# automatic_Slider_door_2.net
KiCad netlist of a schematic drawn in EAGLE
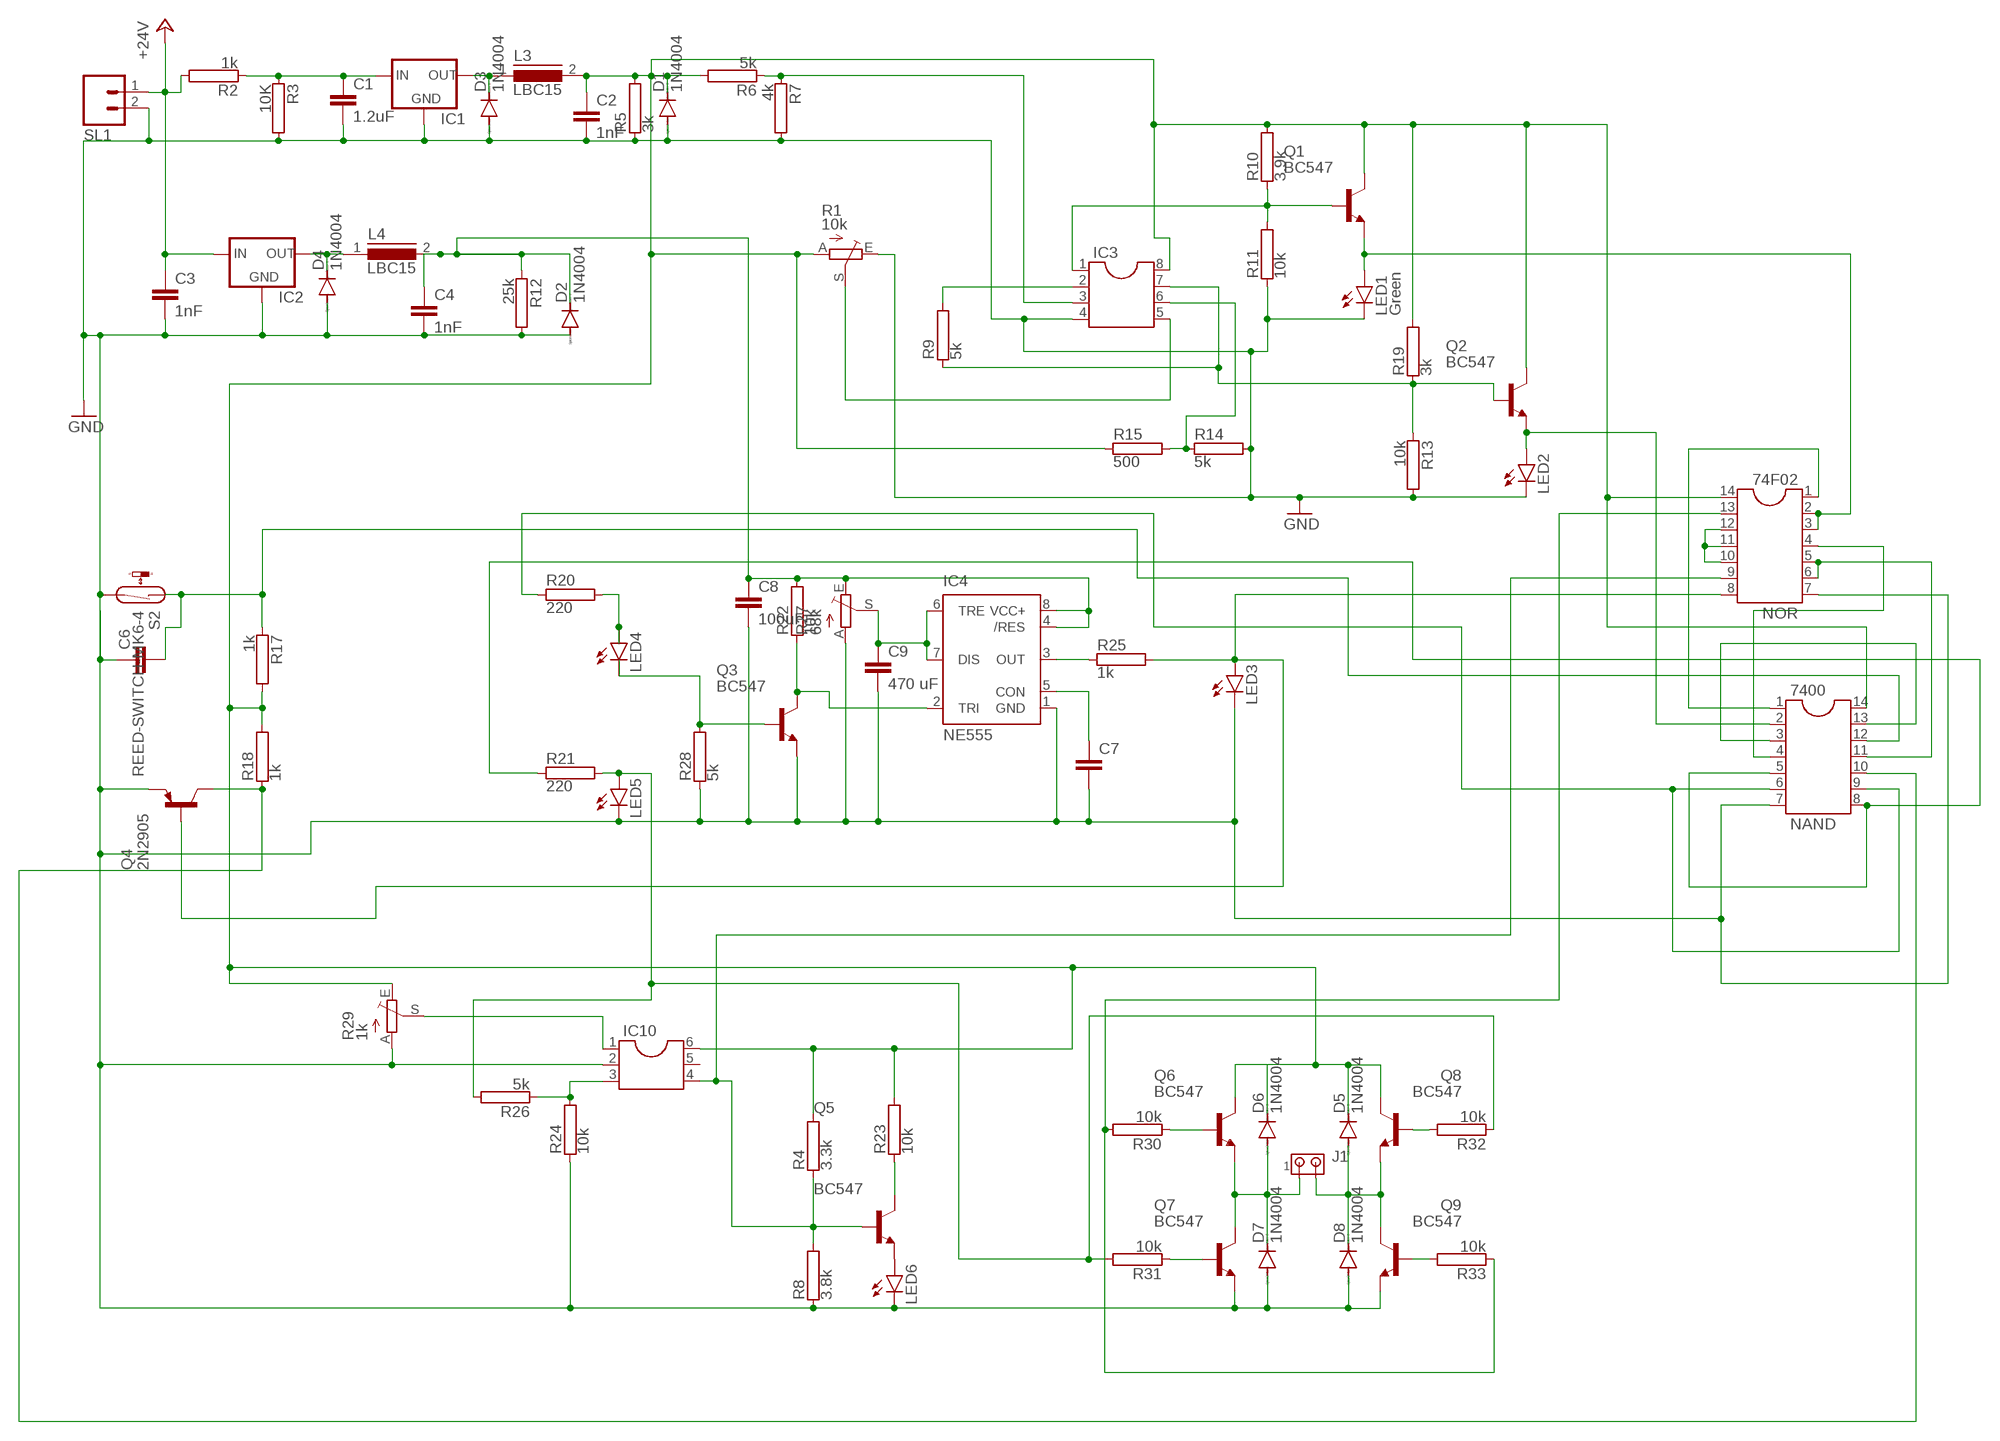
[diagram p0: schematic, sheet 1]

(export (version "E")
  (design (tool "Eeschema 10.0.6"))
  (components
    (comp (ref "74F02")
      (value "NOR")
      (footprint "eagle-import:DIL14")
      (libsource (lib "eagle-import") (part "DIL14"))
    )
    (comp (ref "7400")
      (value "NAND")
      (footprint "eagle-import:DIL14")
      (libsource (lib "eagle-import") (part "DIL14"))
    )
    (comp (ref "C1")
      (value "1.2uF")
      (footprint "eagle-import:C2.5-3")
      (libsource (lib "eagle-import") (part "C2,5-3"))
    )
    (comp (ref "C2")
      (value "1nF")
      (footprint "eagle-import:C2.5-3")
      (libsource (lib "eagle-import") (part "C2,5-3"))
    )
    (comp (ref "C3")
      (value "1nF")
      (footprint "eagle-import:C2.5-3")
      (libsource (lib "eagle-import") (part "C2,5-3"))
    )
    (comp (ref "C4")
      (value "1nF")
      (footprint "eagle-import:C2.5-3")
      (libsource (lib "eagle-import") (part "C2,5-3"))
    )
    (comp (ref "C6")
      (value "C2,5-3")
      (footprint "eagle-import:C2.5-3")
      (libsource (lib "eagle-import") (part "C2,5-3"))
    )
    (comp (ref "C7")
      (value "C2,5-3")
      (footprint "eagle-import:C2.5-3")
      (libsource (lib "eagle-import") (part "C2,5-3"))
    )
    (comp (ref "C8")
      (value "100uF")
      (footprint "eagle-import:C2.5-3")
      (libsource (lib "eagle-import") (part "C2,5-3"))
    )
    (comp (ref "C9")
      (value "470 uF")
      (footprint "eagle-import:C2.5-3")
      (libsource (lib "eagle-import") (part "C2,5-3"))
    )
    (comp (ref "D1")
      (value "1N4004")
      (footprint "eagle-import:DO41-10")
      (libsource (lib "eagle-import") (part "1N4004"))
    )
    (comp (ref "D2")
      (value "1N4004")
      (footprint "eagle-import:DO41-10")
      (libsource (lib "eagle-import") (part "1N4004"))
    )
    (comp (ref "D3")
      (value "1N4004")
      (footprint "eagle-import:DO41-10")
      (libsource (lib "eagle-import") (part "1N4004"))
    )
    (comp (ref "D4")
      (value "1N4004")
      (footprint "eagle-import:DO41-10")
      (libsource (lib "eagle-import") (part "1N4004"))
    )
    (comp (ref "D5")
      (value "1N4004")
      (footprint "eagle-import:DO41-10")
      (libsource (lib "eagle-import") (part "1N4004"))
    )
    (comp (ref "D6")
      (value "1N4004")
      (footprint "eagle-import:DO41-10")
      (libsource (lib "eagle-import") (part "1N4004"))
    )
    (comp (ref "D7")
      (value "1N4004")
      (footprint "eagle-import:DO41-10")
      (libsource (lib "eagle-import") (part "1N4004"))
    )
    (comp (ref "D8")
      (value "1N4004")
      (footprint "eagle-import:DO41-10")
      (libsource (lib "eagle-import") (part "1N4004"))
    )
    (comp (ref "IC1")
      (value "78LXX")
      (footprint "eagle-import:78LXX")
      (libsource (lib "eagle-import") (part "78LXX"))
    )
    (comp (ref "IC2")
      (value "78LXX")
      (footprint "eagle-import:78LXX")
      (libsource (lib "eagle-import") (part "78LXX"))
    )
    (comp (ref "IC3")
      (value "DIL8S")
      (footprint "eagle-import:SOCKET-08")
      (libsource (lib "eagle-import") (part "DIL8S"))
    )
    (comp (ref "IC4")
      (value "NE555")
      (footprint "eagle-import:DIL-08")
      (fields (field (name "MF") "Arrow Electronics") (field (name "MPN") "NE555N"))
      (libsource (lib "eagle-import") (part "NE555"))
    )
    (comp (ref "IC10")
      (value "DIL6S")
      (footprint "eagle-import:SOCKET-06")
      (libsource (lib "eagle-import") (part "DIL6S"))
    )
    (comp (ref "J1")
      (value "MTA02-156")
      (footprint "eagle-import:1X2MTA")
      (libsource (lib "eagle-import") (part "MTA02-156"))
    )
    (comp (ref "L3")
      (value "LBC15")
      (footprint "eagle-import:LBC15")
      (libsource (lib "eagle-import") (part "LBC15"))
    )
    (comp (ref "L4")
      (value "LBC15")
      (footprint "eagle-import:LBC15")
      (libsource (lib "eagle-import") (part "LBC15"))
    )
    (comp (ref "LED1")
      (value "Green")
      (footprint "eagle-import:Q62902-B152")
      (libsource (lib "eagle-import") (part "LEDB152"))
    )
    (comp (ref "LED2")
      (value "LEDB152")
      (footprint "eagle-import:Q62902-B152")
      (libsource (lib "eagle-import") (part "LEDB152"))
    )
    (comp (ref "LED3")
      (value "LEDB152")
      (footprint "eagle-import:Q62902-B152")
      (libsource (lib "eagle-import") (part "LEDB152"))
    )
    (comp (ref "LED4")
      (value "LEDB152")
      (footprint "eagle-import:Q62902-B152")
      (libsource (lib "eagle-import") (part "LEDB152"))
    )
    (comp (ref "LED5")
      (value "LEDB152")
      (footprint "eagle-import:Q62902-B152")
      (libsource (lib "eagle-import") (part "LEDB152"))
    )
    (comp (ref "LED6")
      (value "LEDB152")
      (footprint "eagle-import:Q62902-B152")
      (libsource (lib "eagle-import") (part "LEDB152"))
    )
    (comp (ref "Q1")
      (value "BC547")
      (footprint "eagle-import:TO92")
      (libsource (lib "eagle-import") (part "BC547"))
    )
    (comp (ref "Q2")
      (value "BC547")
      (footprint "eagle-import:TO92")
      (libsource (lib "eagle-import") (part "BC547"))
    )
    (comp (ref "Q3")
      (value "BC547")
      (footprint "eagle-import:TO92")
      (libsource (lib "eagle-import") (part "BC547"))
    )
    (comp (ref "Q4")
      (value "2N2905")
      (footprint "eagle-import:TO5")
      (libsource (lib "eagle-import") (part "2N2905"))
    )
    (comp (ref "Q5")
      (value "BC547")
      (footprint "eagle-import:TO92")
      (libsource (lib "eagle-import") (part "BC547"))
    )
    (comp (ref "Q6")
      (value "BC547")
      (footprint "eagle-import:TO92")
      (libsource (lib "eagle-import") (part "BC547"))
    )
    (comp (ref "Q7")
      (value "BC547")
      (footprint "eagle-import:TO92")
      (libsource (lib "eagle-import") (part "BC547"))
    )
    (comp (ref "Q8")
      (value "BC547")
      (footprint "eagle-import:TO92")
      (libsource (lib "eagle-import") (part "BC547"))
    )
    (comp (ref "Q9")
      (value "BC547")
      (footprint "eagle-import:TO92")
      (libsource (lib "eagle-import") (part "BC547"))
    )
    (comp (ref "R1")
      (value "10k")
      (footprint "eagle-import:S75P")
      (libsource (lib "eagle-import") (part "TRIM_EU-S75P"))
    )
    (comp (ref "R2")
      (value "1k")
      (footprint "eagle-import:CA0001")
      (libsource (lib "eagle-import") (part "RCA0001"))
    )
    (comp (ref "R3")
      (value "10K")
      (footprint "eagle-import:CA0001")
      (libsource (lib "eagle-import") (part "RCA0001"))
    )
    (comp (ref "R4")
      (value "3.3k")
      (footprint "eagle-import:CA0001")
      (libsource (lib "eagle-import") (part "RCA0001"))
    )
    (comp (ref "R5")
      (value "3k")
      (footprint "eagle-import:CA0001")
      (libsource (lib "eagle-import") (part "RCA0001"))
    )
    (comp (ref "R6")
      (value "5k")
      (footprint "eagle-import:CA0001")
      (libsource (lib "eagle-import") (part "RCA0001"))
    )
    (comp (ref "R7")
      (value "4k")
      (footprint "eagle-import:CA0001")
      (libsource (lib "eagle-import") (part "RCA0001"))
    )
    (comp (ref "R8")
      (value "3.8k")
      (footprint "eagle-import:CA0001")
      (libsource (lib "eagle-import") (part "RCA0001"))
    )
    (comp (ref "R9")
      (value "5k")
      (footprint "eagle-import:CA0001")
      (libsource (lib "eagle-import") (part "RCA0001"))
    )
    (comp (ref "R10")
      (value "3.9k")
      (footprint "eagle-import:CA0001")
      (libsource (lib "eagle-import") (part "RCA0001"))
    )
    (comp (ref "R11")
      (value "10k")
      (footprint "eagle-import:CA0001")
      (libsource (lib "eagle-import") (part "RCA0001"))
    )
    (comp (ref "R12")
      (value "25k")
      (footprint "eagle-import:CA0001")
      (libsource (lib "eagle-import") (part "RCA0001"))
    )
    (comp (ref "R13")
      (value "10k")
      (footprint "eagle-import:CA0001")
      (libsource (lib "eagle-import") (part "RCA0001"))
    )
    (comp (ref "R14")
      (value "5k")
      (footprint "eagle-import:CA0001")
      (libsource (lib "eagle-import") (part "RCA0001"))
    )
    (comp (ref "R15")
      (value "500")
      (footprint "eagle-import:CA0001")
      (libsource (lib "eagle-import") (part "RCA0001"))
    )
    (comp (ref "R17")
      (value "1k")
      (footprint "eagle-import:CA0001")
      (libsource (lib "eagle-import") (part "RCA0001"))
    )
    (comp (ref "R18")
      (value "1k")
      (footprint "eagle-import:CA0001")
      (libsource (lib "eagle-import") (part "RCA0001"))
    )
    (comp (ref "R19")
      (value "3k")
      (footprint "eagle-import:CA0001")
      (libsource (lib "eagle-import") (part "RCA0001"))
    )
    (comp (ref "R20")
      (value "220")
      (footprint "eagle-import:CA0001")
      (libsource (lib "eagle-import") (part "RCA0001"))
    )
    (comp (ref "R21")
      (value "220")
      (footprint "eagle-import:CA0001")
      (libsource (lib "eagle-import") (part "RCA0001"))
    )
    (comp (ref "R22")
      (value "10k")
      (footprint "eagle-import:CA0001")
      (libsource (lib "eagle-import") (part "RCA0001"))
    )
    (comp (ref "R23")
      (value "10k")
      (footprint "eagle-import:CA0001")
      (libsource (lib "eagle-import") (part "RCA0001"))
    )
    (comp (ref "R24")
      (value "10k")
      (footprint "eagle-import:CA0001")
      (libsource (lib "eagle-import") (part "RCA0001"))
    )
    (comp (ref "R25")
      (value "1k")
      (footprint "eagle-import:CA0001")
      (libsource (lib "eagle-import") (part "RCA0001"))
    )
    (comp (ref "R26")
      (value "5k")
      (footprint "eagle-import:CA0001")
      (libsource (lib "eagle-import") (part "RCA0001"))
    )
    (comp (ref "R27")
      (value "68k")
      (footprint "eagle-import:S75P")
      (libsource (lib "eagle-import") (part "TRIM_EU-S75P"))
    )
    (comp (ref "R28")
      (value "5k")
      (footprint "eagle-import:CA0001")
      (libsource (lib "eagle-import") (part "RCA0001"))
    )
    (comp (ref "R29")
      (value "1k")
      (footprint "eagle-import:S75P")
      (libsource (lib "eagle-import") (part "TRIM_EU-S75P"))
    )
    (comp (ref "R30")
      (value "10k")
      (footprint "eagle-import:CA0001")
      (libsource (lib "eagle-import") (part "RCA0001"))
    )
    (comp (ref "R31")
      (value "10k")
      (footprint "eagle-import:CA0001")
      (libsource (lib "eagle-import") (part "RCA0001"))
    )
    (comp (ref "R32")
      (value "10k")
      (footprint "eagle-import:CA0001")
      (libsource (lib "eagle-import") (part "RCA0001"))
    )
    (comp (ref "R33")
      (value "10k")
      (footprint "eagle-import:CA0001")
      (libsource (lib "eagle-import") (part "RCA0001"))
    )
    (comp (ref "S2")
      (value "REED-SWITCH-MK6-4")
      (footprint "eagle-import:MK6-4")
      (libsource (lib "eagle-import") (part "REED-SWITCH-MK6-4"))
    )
    (comp (ref "SL1")
      (value "MA02")
      (footprint "eagle-import:02PA")
      (libsource (lib "eagle-import") (part "MA02"))
    )
  )
  (nets
    (net (code "1") (name "+24V") (class "Default")
      (node (ref "C3") (pin "1") (pinfunction "1_1") (pintype "passive"))
      (node (ref "IC2") (pin "IN") (pinfunction "IN_IN") (pintype "input"))
      (node (ref "R2") (pin "2") (pinfunction "2_2") (pintype "passive"))
      (node (ref "SL1") (pin "1") (pinfunction "1_1") (pintype "passive"))
    )
    (net (code "2") (name "GND") (class "Default")
      (node (ref "7400") (pin "7") (pinfunction "7_7") (pintype "passive"))
      (node (ref "74F02") (pin "7") (pinfunction "7_7") (pintype "passive"))
      (node (ref "C1") (pin "2") (pinfunction "2_2") (pintype "passive"))
      (node (ref "C2") (pin "2") (pinfunction "2_2") (pintype "passive"))
      (node (ref "C3") (pin "2") (pinfunction "2_2") (pintype "passive"))
      (node (ref "C4") (pin "2") (pinfunction "2_2") (pintype "passive"))
      (node (ref "C6") (pin "1") (pinfunction "1_1") (pintype "passive"))
      (node (ref "C7") (pin "2") (pinfunction "2_2") (pintype "passive"))
      (node (ref "C8") (pin "2") (pinfunction "2_2") (pintype "passive"))
      (node (ref "C9") (pin "2") (pinfunction "2_2") (pintype "passive"))
      (node (ref "D1") (pin "A") (pinfunction "A_A") (pintype "passive"))
      (node (ref "D2") (pin "A") (pinfunction "A_A") (pintype "passive"))
      (node (ref "D3") (pin "A") (pinfunction "A_A") (pintype "passive"))
      (node (ref "D4") (pin "A") (pinfunction "A_A") (pintype "passive"))
      (node (ref "D7") (pin "A") (pinfunction "A_A") (pintype "passive"))
      (node (ref "D8") (pin "A") (pinfunction "A_A") (pintype "passive"))
      (node (ref "IC1") (pin "GND") (pinfunction "GND_GND") (pintype "input"))
      (node (ref "IC10") (pin "2") (pinfunction "2_2") (pintype "passive"))
      (node (ref "IC2") (pin "GND") (pinfunction "GND_GND") (pintype "input"))
      (node (ref "IC3") (pin "4") (pinfunction "4_4") (pintype "passive"))
      (node (ref "IC4") (pin "1") (pinfunction "GND_1") (pintype "power_in"))
      (node (ref "LED1") (pin "K") (pinfunction "C_K") (pintype "passive"))
      (node (ref "LED2") (pin "K") (pinfunction "C_K") (pintype "passive"))
      (node (ref "LED3") (pin "K") (pinfunction "C_K") (pintype "passive"))
      (node (ref "LED5") (pin "K") (pinfunction "C_K") (pintype "passive"))
      (node (ref "LED6") (pin "K") (pinfunction "C_K") (pintype "passive"))
      (node (ref "Q3") (pin "1") (pinfunction "E_1") (pintype "passive"))
      (node (ref "Q4") (pin "1") (pinfunction "E_1") (pintype "passive"))
      (node (ref "Q7") (pin "1") (pinfunction "E_1") (pintype "passive"))
      (node (ref "Q9") (pin "1") (pinfunction "E_1") (pintype "passive"))
      (node (ref "R1") (pin "E") (pinfunction "E_E") (pintype "passive"))
      (node (ref "R11") (pin "1") (pinfunction "1_1") (pintype "passive"))
      (node (ref "R12") (pin "2") (pinfunction "2_2") (pintype "passive"))
      (node (ref "R13") (pin "2") (pinfunction "2_2") (pintype "passive"))
      (node (ref "R14") (pin "2") (pinfunction "2_2") (pintype "passive"))
      (node (ref "R24") (pin "1") (pinfunction "1_1") (pintype "passive"))
      (node (ref "R27") (pin "A") (pinfunction "A_A") (pintype "passive"))
      (node (ref "R28") (pin "1") (pinfunction "1_1") (pintype "passive"))
      (node (ref "R29") (pin "A") (pinfunction "A_A") (pintype "passive"))
      (node (ref "R3") (pin "2") (pinfunction "2_2") (pintype "passive"))
      (node (ref "R5") (pin "1") (pinfunction "1_1") (pintype "passive"))
      (node (ref "R7") (pin "2") (pinfunction "2_2") (pintype "passive"))
      (node (ref "R8") (pin "1") (pinfunction "1_1") (pintype "passive"))
      (node (ref "S2") (pin "2") (pinfunction "2_2") (pintype "passive"))
      (node (ref "SL1") (pin "2") (pinfunction "2_2") (pintype "passive"))
    )
    (net (code "3") (name "Net-(74F02-Pad10)") (class "Default")
      (node (ref "74F02") (pin "10") (pinfunction "10_10") (pintype "passive"))
      (node (ref "74F02") (pin "11") (pinfunction "11_11") (pintype "passive"))
      (node (ref "74F02") (pin "12") (pinfunction "12_12") (pintype "passive"))
    )
    (net (code "4") (name "Net-(74F02-Pad13)") (class "Default")
      (node (ref "74F02") (pin "13") (pinfunction "13_13") (pintype "passive"))
      (node (ref "R30") (pin "2") (pinfunction "2_2") (pintype "passive"))
      (node (ref "R33") (pin "1") (pinfunction "1_1") (pintype "passive"))
    )
    (net (code "5") (name "Net-(7400-Pad1)") (class "Default")
      (node (ref "7400") (pin "1") (pinfunction "1_1") (pintype "passive"))
      (node (ref "74F02") (pin "1") (pinfunction "1_1") (pintype "passive"))
    )
    (net (code "6") (name "Net-(7400-Pad4)") (class "Default")
      (node (ref "7400") (pin "4") (pinfunction "4_4") (pintype "passive"))
      (node (ref "74F02") (pin "4") (pinfunction "4_4") (pintype "passive"))
    )
    (net (code "7") (name "Net-(7400-Pad5)") (class "Default")
      (node (ref "7400") (pin "5") (pinfunction "5_5") (pintype "passive"))
      (node (ref "7400") (pin "8") (pinfunction "8_8") (pintype "passive"))
      (node (ref "R21") (pin "1") (pinfunction "1_1") (pintype "passive"))
    )
    (net (code "8") (name "Net-(7400-Pad6)") (class "Default")
      (node (ref "7400") (pin "6") (pinfunction "6_6") (pintype "passive"))
      (node (ref "7400") (pin "9") (pinfunction "9_9") (pintype "passive"))
      (node (ref "R20") (pin "1") (pinfunction "1_1") (pintype "passive"))
    )
    (net (code "9") (name "Net-(7400-Pad11)") (class "Default")
      (node (ref "7400") (pin "11") (pinfunction "11_11") (pintype "passive"))
      (node (ref "74F02") (pin "5") (pinfunction "5_5") (pintype "passive"))
      (node (ref "74F02") (pin "6") (pinfunction "6_6") (pintype "passive"))
    )
    (net (code "10") (name "Net-(7400-Pad12)") (class "Default")
      (node (ref "7400") (pin "12") (pinfunction "12_12") (pintype "passive"))
      (node (ref "C6") (pin "2") (pinfunction "2_2") (pintype "passive"))
      (node (ref "R17") (pin "1") (pinfunction "1_1") (pintype "passive"))
      (node (ref "S2") (pin "1") (pinfunction "1_1") (pintype "passive"))
    )
    (net (code "11") (name "Net-(7400-Pad13)") (class "Default")
      (node (ref "7400") (pin "13") (pinfunction "13_13") (pintype "passive"))
      (node (ref "7400") (pin "3") (pinfunction "3_3") (pintype "passive"))
    )
    (net (code "12") (name "Net-(C1-Pad1)") (class "Default")
      (node (ref "C1") (pin "1") (pinfunction "1_1") (pintype "passive"))
      (node (ref "IC1") (pin "IN") (pinfunction "IN_IN") (pintype "input"))
      (node (ref "R2") (pin "1") (pinfunction "1_1") (pintype "passive"))
      (node (ref "R3") (pin "1") (pinfunction "1_1") (pintype "passive"))
    )
    (net (code "13") (name "Net-(D3-PadC)") (class "Default")
      (node (ref "D3") (pin "C") (pinfunction "C_C") (pintype "passive"))
      (node (ref "IC1") (pin "OUT") (pinfunction "OUT_OUT") (pintype "passive"))
      (node (ref "L3") (pin "1") (pinfunction "1_1") (pintype "passive"))
    )
    (net (code "14") (name "Net-(D4-PadC)") (class "Default")
      (node (ref "D4") (pin "C") (pinfunction "C_C") (pintype "passive"))
      (node (ref "IC2") (pin "OUT") (pinfunction "OUT_OUT") (pintype "passive"))
      (node (ref "L4") (pin "1") (pinfunction "1_1") (pintype "passive"))
    )
    (net (code "15") (name "Net-(IC3-Pad2)") (class "Default")
      (node (ref "IC3") (pin "2") (pinfunction "2_2") (pintype "passive"))
      (node (ref "R9") (pin "2") (pinfunction "2_2") (pintype "passive"))
    )
    (net (code "16") (name "Net-(IC3-Pad3)") (class "Default")
      (node (ref "IC3") (pin "3") (pinfunction "3_3") (pintype "passive"))
      (node (ref "R6") (pin "1") (pinfunction "1_1") (pintype "passive"))
      (node (ref "R7") (pin "1") (pinfunction "1_1") (pintype "passive"))
    )
    (net (code "17") (name "Net-(IC3-Pad5)") (class "Default")
      (node (ref "IC3") (pin "5") (pinfunction "5_5") (pintype "passive"))
      (node (ref "R1") (pin "S") (pinfunction "S_S") (pintype "passive"))
    )
    (net (code "18") (name "Net-(IC3-Pad6)") (class "Default")
      (node (ref "IC3") (pin "6") (pinfunction "6_6") (pintype "passive"))
      (node (ref "R14") (pin "1") (pinfunction "1_1") (pintype "passive"))
      (node (ref "R15") (pin "2") (pinfunction "2_2") (pintype "passive"))
    )
    (net (code "19") (name "Net-(IC4-CON)") (class "Default")
      (node (ref "C7") (pin "1") (pinfunction "1_1") (pintype "passive"))
      (node (ref "IC4") (pin "5") (pinfunction "CON_5") (pintype "input"))
    )
    (net (code "20") (name "Net-(IC4-DIS)") (class "Default")
      (node (ref "C9") (pin "1") (pinfunction "1_1") (pintype "passive"))
      (node (ref "IC4") (pin "6") (pinfunction "TRE_6") (pintype "input"))
      (node (ref "IC4") (pin "7") (pinfunction "DIS_7") (pintype "input"))
      (node (ref "R27") (pin "S") (pinfunction "S_S") (pintype "passive"))
    )
    (net (code "21") (name "Net-(IC4-OUT)") (class "Default")
      (node (ref "IC4") (pin "3") (pinfunction "OUT_3") (pintype "output"))
      (node (ref "R25") (pin "1") (pinfunction "1_1") (pintype "passive"))
    )
    (net (code "22") (name "Net-(IC4-TRI)") (class "Default")
      (node (ref "IC4") (pin "2") (pinfunction "TRI_2") (pintype "input"))
      (node (ref "Q3") (pin "3") (pinfunction "C_3") (pintype "passive"))
      (node (ref "R22") (pin "1") (pinfunction "1_1") (pintype "passive"))
    )
    (net (code "23") (name "Net-(IC4-VCC+)") (class "Default")
      (node (ref "C4") (pin "1") (pinfunction "1_1") (pintype "passive"))
      (node (ref "C8") (pin "1") (pinfunction "1_1") (pintype "passive"))
      (node (ref "D2") (pin "C") (pinfunction "C_C") (pintype "passive"))
      (node (ref "IC4") (pin "4") (pinfunction "/RES_4") (pintype "input"))
      (node (ref "IC4") (pin "8") (pinfunction "VCC+_8") (pintype "power_in"))
      (node (ref "L4") (pin "2") (pinfunction "2_2") (pintype "passive"))
      (node (ref "R12") (pin "1") (pinfunction "1_1") (pintype "passive"))
      (node (ref "R22") (pin "2") (pinfunction "2_2") (pintype "passive"))
      (node (ref "R27") (pin "E") (pinfunction "E_E") (pintype "passive"))
    )
    (net (code "24") (name "Net-(IC10-Pad1)") (class "Default")
      (node (ref "IC10") (pin "1") (pinfunction "1_1") (pintype "passive"))
      (node (ref "R29") (pin "S") (pinfunction "S_S") (pintype "passive"))
    )
    (net (code "25") (name "Net-(IC10-Pad3)") (class "Default")
      (node (ref "IC10") (pin "3") (pinfunction "3_3") (pintype "passive"))
      (node (ref "R24") (pin "2") (pinfunction "2_2") (pintype "passive"))
      (node (ref "R26") (pin "1") (pinfunction "1_1") (pintype "passive"))
    )
    (net (code "26") (name "Net-(LED4-C)") (class "Default")
      (node (ref "LED4") (pin "K") (pinfunction "C_K") (pintype "passive"))
      (node (ref "Q3") (pin "2") (pinfunction "B_2") (pintype "passive"))
      (node (ref "R28") (pin "2") (pinfunction "2_2") (pintype "passive"))
    )
    (net (code "27") (name "Net-(LED4-PadA)") (class "Default")
      (node (ref "LED4") (pin "A") (pinfunction "A_A") (pintype "passive"))
      (node (ref "R20") (pin "2") (pinfunction "2_2") (pintype "passive"))
    )
    (net (code "28") (name "Net-(LED5-PadA)") (class "Default")
      (node (ref "LED5") (pin "A") (pinfunction "A_A") (pintype "passive"))
      (node (ref "R21") (pin "2") (pinfunction "2_2") (pintype "passive"))
      (node (ref "R26") (pin "2") (pinfunction "2_2") (pintype "passive"))
      (node (ref "R31") (pin "2") (pinfunction "2_2") (pintype "passive"))
      (node (ref "R32") (pin "1") (pinfunction "1_1") (pintype "passive"))
    )
    (net (code "29") (name "Net-(Q1-B)") (class "Default")
      (node (ref "IC3") (pin "1") (pinfunction "1_1") (pintype "passive"))
      (node (ref "Q1") (pin "2") (pinfunction "B_2") (pintype "passive"))
      (node (ref "R10") (pin "1") (pinfunction "1_1") (pintype "passive"))
      (node (ref "R11") (pin "2") (pinfunction "2_2") (pintype "passive"))
    )
    (net (code "30") (name "Net-(Q1-C)") (class "Default")
      (node (ref "7400") (pin "14") (pinfunction "14_14") (pintype "passive"))
      (node (ref "74F02") (pin "14") (pinfunction "14_14") (pintype "passive"))
      (node (ref "C2") (pin "1") (pinfunction "1_1") (pintype "passive"))
      (node (ref "D1") (pin "C") (pinfunction "C_C") (pintype "passive"))
      (node (ref "D5") (pin "C") (pinfunction "C_C") (pintype "passive"))
      (node (ref "D6") (pin "C") (pinfunction "C_C") (pintype "passive"))
      (node (ref "IC10") (pin "6") (pinfunction "6_6") (pintype "passive"))
      (node (ref "IC3") (pin "8") (pinfunction "8_8") (pintype "passive"))
      (node (ref "L3") (pin "2") (pinfunction "2_2") (pintype "passive"))
      (node (ref "Q1") (pin "3") (pinfunction "C_3") (pintype "passive"))
      (node (ref "Q2") (pin "3") (pinfunction "C_3") (pintype "passive"))
      (node (ref "Q6") (pin "3") (pinfunction "C_3") (pintype "passive"))
      (node (ref "Q8") (pin "3") (pinfunction "C_3") (pintype "passive"))
      (node (ref "R1") (pin "A") (pinfunction "A_A") (pintype "passive"))
      (node (ref "R10") (pin "2") (pinfunction "2_2") (pintype "passive"))
      (node (ref "R15") (pin "1") (pinfunction "1_1") (pintype "passive"))
      (node (ref "R17") (pin "2") (pinfunction "2_2") (pintype "passive"))
      (node (ref "R18") (pin "2") (pinfunction "2_2") (pintype "passive"))
      (node (ref "R19") (pin "2") (pinfunction "2_2") (pintype "passive"))
      (node (ref "R23") (pin "2") (pinfunction "2_2") (pintype "passive"))
      (node (ref "R29") (pin "E") (pinfunction "E_E") (pintype "passive"))
      (node (ref "R4") (pin "2") (pinfunction "2_2") (pintype "passive"))
      (node (ref "R5") (pin "2") (pinfunction "2_2") (pintype "passive"))
      (node (ref "R6") (pin "2") (pinfunction "2_2") (pintype "passive"))
    )
    (net (code "31") (name "Net-(Q1-E)") (class "Default")
      (node (ref "74F02") (pin "2") (pinfunction "2_2") (pintype "passive"))
      (node (ref "74F02") (pin "3") (pinfunction "3_3") (pintype "passive"))
      (node (ref "LED1") (pin "A") (pinfunction "A_A") (pintype "passive"))
      (node (ref "Q1") (pin "1") (pinfunction "E_1") (pintype "passive"))
    )
    (net (code "32") (name "Net-(Q2-B)") (class "Default")
      (node (ref "IC3") (pin "7") (pinfunction "7_7") (pintype "passive"))
      (node (ref "Q2") (pin "2") (pinfunction "B_2") (pintype "passive"))
      (node (ref "R13") (pin "1") (pinfunction "1_1") (pintype "passive"))
      (node (ref "R19") (pin "1") (pinfunction "1_1") (pintype "passive"))
      (node (ref "R9") (pin "1") (pinfunction "1_1") (pintype "passive"))
    )
    (net (code "33") (name "Net-(Q2-E)") (class "Default")
      (node (ref "7400") (pin "2") (pinfunction "2_2") (pintype "passive"))
      (node (ref "LED2") (pin "A") (pinfunction "A_A") (pintype "passive"))
      (node (ref "Q2") (pin "1") (pinfunction "E_1") (pintype "passive"))
    )
    (net (code "34") (name "Net-(Q4-B)") (class "Default")
      (node (ref "74F02") (pin "8") (pinfunction "8_8") (pintype "passive"))
      (node (ref "LED3") (pin "A") (pinfunction "A_A") (pintype "passive"))
      (node (ref "Q4") (pin "2") (pinfunction "B_2") (pintype "passive"))
      (node (ref "R25") (pin "2") (pinfunction "2_2") (pintype "passive"))
    )
    (net (code "35") (name "Net-(Q4-C)") (class "Default")
      (node (ref "7400") (pin "10") (pinfunction "10_10") (pintype "passive"))
      (node (ref "Q4") (pin "3") (pinfunction "C_3") (pintype "passive"))
      (node (ref "R18") (pin "1") (pinfunction "1_1") (pintype "passive"))
    )
    (net (code "36") (name "Net-(Q5-B)") (class "Default")
      (node (ref "74F02") (pin "9") (pinfunction "9_9") (pintype "passive"))
      (node (ref "IC10") (pin "4") (pinfunction "4_4") (pintype "passive"))
      (node (ref "Q5") (pin "2") (pinfunction "B_2") (pintype "passive"))
      (node (ref "R4") (pin "1") (pinfunction "1_1") (pintype "passive"))
      (node (ref "R8") (pin "2") (pinfunction "2_2") (pintype "passive"))
    )
    (net (code "37") (name "Net-(Q5-C)") (class "Default")
      (node (ref "Q5") (pin "3") (pinfunction "C_3") (pintype "passive"))
      (node (ref "R23") (pin "1") (pinfunction "1_1") (pintype "passive"))
    )
    (net (code "38") (name "Net-(Q5-E)") (class "Default")
      (node (ref "LED6") (pin "A") (pinfunction "A_A") (pintype "passive"))
      (node (ref "Q5") (pin "1") (pinfunction "E_1") (pintype "passive"))
    )
    (net (code "39") (name "Net-(Q6-B)") (class "Default")
      (node (ref "Q6") (pin "2") (pinfunction "B_2") (pintype "passive"))
      (node (ref "R30") (pin "1") (pinfunction "1_1") (pintype "passive"))
    )
    (net (code "40") (name "Net-(Q6-E)") (class "Default")
      (node (ref "D6") (pin "A") (pinfunction "A_A") (pintype "passive"))
      (node (ref "D7") (pin "C") (pinfunction "C_C") (pintype "passive"))
      (node (ref "J1") (pin "1") (pinfunction "1_1") (pintype "passive"))
      (node (ref "Q6") (pin "1") (pinfunction "E_1") (pintype "passive"))
      (node (ref "Q7") (pin "3") (pinfunction "C_3") (pintype "passive"))
    )
    (net (code "41") (name "Net-(Q7-B)") (class "Default")
      (node (ref "Q7") (pin "2") (pinfunction "B_2") (pintype "passive"))
      (node (ref "R31") (pin "1") (pinfunction "1_1") (pintype "passive"))
    )
    (net (code "42") (name "Net-(Q8-B)") (class "Default")
      (node (ref "Q8") (pin "2") (pinfunction "B_2") (pintype "passive"))
      (node (ref "R32") (pin "2") (pinfunction "2_2") (pintype "passive"))
    )
    (net (code "43") (name "Net-(Q8-E)") (class "Default")
      (node (ref "D5") (pin "A") (pinfunction "A_A") (pintype "passive"))
      (node (ref "D8") (pin "C") (pinfunction "C_C") (pintype "passive"))
      (node (ref "J1") (pin "2") (pinfunction "2_2") (pintype "passive"))
      (node (ref "Q8") (pin "1") (pinfunction "E_1") (pintype "passive"))
      (node (ref "Q9") (pin "3") (pinfunction "C_3") (pintype "passive"))
    )
    (net (code "44") (name "Net-(Q9-B)") (class "Default")
      (node (ref "Q9") (pin "2") (pinfunction "B_2") (pintype "passive"))
      (node (ref "R33") (pin "2") (pinfunction "2_2") (pintype "passive"))
    )
    (net (code "45") (name "unconnected-(IC10-Pad5)") (class "Default")
      (node (ref "IC10") (pin "5") (pinfunction "5_5") (pintype "passive"))
    )
  )
)
